# Power.net
KiCad netlist of a schematic drawn in Altium Designer
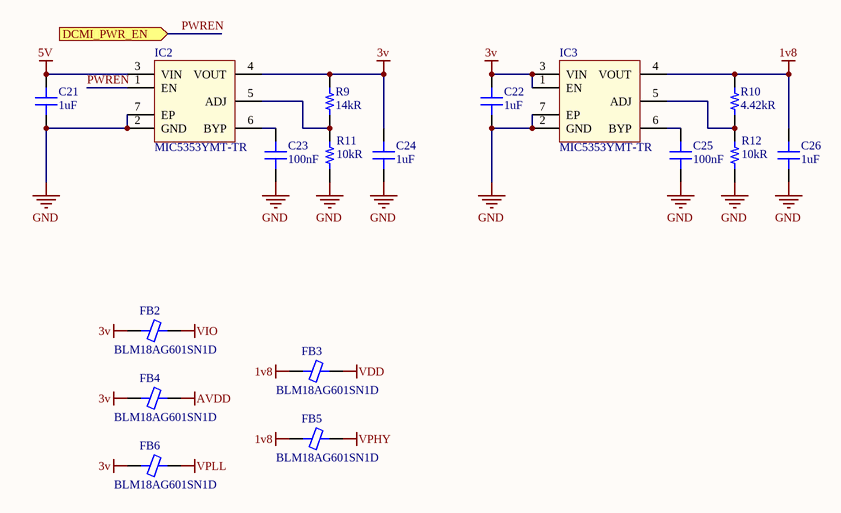
[diagram p0: Power.SchDoc]

(export (version "E")
  (design (tool "Eeschema 10.0.6"))
  (components
    (comp (ref "C21")
      (value "1uF")
      (footprint "CAP 0603/1608")
      (description "Ceramic, SMT Capacitor")
      (fields
        (field (name "MANUFACTURER") "Samsung")
        (field (name "MANUFACTURER PART NUMBER") "CL10A105KP8NNNC")
      )
      (libsource (lib "yildizIoT Library") (part "Capacitor - Ceramic"))
    )
    (comp (ref "C22")
      (value "1uF")
      (footprint "CAP 0603/1608")
      (description "Ceramic, SMT Capacitor")
      (fields
        (field (name "MANUFACTURER") "Samsung")
        (field (name "MANUFACTURER PART NUMBER") "CL10A105KP8NNNC")
      )
      (libsource (lib "yildizIoT Library") (part "Capacitor - Ceramic"))
    )
    (comp (ref "C23")
      (value "100nF")
      (footprint "CAP 0603/1608")
      (description "Ceramic, SMT Capacitor")
      (fields
        (field (name "MANUFACTURER") "Samsung")
        (field (name "MANUFACTURER PART NUMBER") "CL10B104JB8NNNC")
      )
      (libsource (lib "yildizIoT Library") (part "Capacitor - Ceramic"))
    )
    (comp (ref "C24")
      (value "1uF")
      (footprint "CAP 0603/1608")
      (description "Ceramic, SMT Capacitor")
      (fields
        (field (name "MANUFACTURER") "Samsung")
        (field (name "MANUFACTURER PART NUMBER") "CL10A105KP8NNNC")
      )
      (libsource (lib "yildizIoT Library") (part "Capacitor - Ceramic"))
    )
    (comp (ref "C25")
      (value "100nF")
      (footprint "CAP 0603/1608")
      (description "Ceramic, SMT Capacitor")
      (fields
        (field (name "MANUFACTURER") "Samsung")
        (field (name "MANUFACTURER PART NUMBER") "CL10B104JB8NNNC")
      )
      (libsource (lib "yildizIoT Library") (part "Capacitor - Ceramic"))
    )
    (comp (ref "C26")
      (value "1uF")
      (footprint "CAP 0603/1608")
      (description "Ceramic, SMT Capacitor")
      (fields
        (field (name "MANUFACTURER") "Samsung")
        (field (name "MANUFACTURER PART NUMBER") "CL10A105KP8NNNC")
      )
      (libsource (lib "yildizIoT Library") (part "Capacitor - Ceramic"))
    )
    (comp (ref "FB2")
      (value "BLM18AG601SN1D")
      (footprint "FER 0603/1608")
      (description "SMT Ferrite Chip")
      (fields (field (name "MANUFACTURER") "Murata") (field (name "TOLERANCE") "25%"))
      (libsource (lib "yildizIoT Library") (part "Ferrite Chip"))
    )
    (comp (ref "FB3")
      (value "BLM18AG601SN1D")
      (footprint "FER 0603/1608")
      (description "SMT Ferrite Chip")
      (fields (field (name "MANUFACTURER") "Murata") (field (name "TOLERANCE") "25%"))
      (libsource (lib "yildizIoT Library") (part "Ferrite Chip"))
    )
    (comp (ref "FB4")
      (value "BLM18AG601SN1D")
      (footprint "FER 0603/1608")
      (description "SMT Ferrite Chip")
      (fields (field (name "MANUFACTURER") "Murata") (field (name "TOLERANCE") "25%"))
      (libsource (lib "yildizIoT Library") (part "Ferrite Chip"))
    )
    (comp (ref "FB5")
      (value "BLM18AG601SN1D")
      (footprint "FER 0603/1608")
      (description "SMT Ferrite Chip")
      (fields (field (name "MANUFACTURER") "Murata") (field (name "TOLERANCE") "25%"))
      (libsource (lib "yildizIoT Library") (part "Ferrite Chip"))
    )
    (comp (ref "FB6")
      (value "BLM18AG601SN1D")
      (footprint "FER 0603/1608")
      (description "SMT Ferrite Chip")
      (fields (field (name "MANUFACTURER") "Murata") (field (name "TOLERANCE") "25%"))
      (libsource (lib "yildizIoT Library") (part "Ferrite Chip"))
    )
    (comp (ref "IC2")
      (value "MIC5353YMT-TR")
      (footprint "MICREL MLF-6 1.6x1.6MM")
      (description "Integrated Circuit")
      (fields (field (name "MANUFACTURER") "Microchip"))
      (libsource (lib "yildizIoT Library") (part "MICROCHIP MIC5353"))
    )
    (comp (ref "IC3")
      (value "MIC5353YMT-TR")
      (footprint "MICREL MLF-6 1.6x1.6MM")
      (description "Integrated Circuit")
      (fields (field (name "MANUFACTURER") "Microchip"))
      (libsource (lib "yildizIoT Library") (part "MICROCHIP MIC5353"))
    )
    (comp (ref "R9")
      (value "14kR")
      (footprint "RES 0603/1608")
      (description "Ceramic, SMT Capacitor")
      (fields
        (field (name "MANUFACTURER") "Yageo")
        (field (name "MANUFACTURER PART NUMBER") "RC0603FR-0714KL")
      )
      (libsource (lib "yildizIoT Library") (part "Resistor_Chip"))
    )
    (comp (ref "R10")
      (value "4.42kR")
      (footprint "RES 0603/1608")
      (description "Ceramic, SMT Capacitor")
      (fields
        (field (name "MANUFACTURER") "Yageo")
        (field (name "MANUFACTURER PART NUMBER") "RC0603FR-074K42L")
      )
      (libsource (lib "yildizIoT Library") (part "Resistor_Chip"))
    )
    (comp (ref "R11")
      (value "10kR")
      (footprint "RES 0603/1608")
      (description "Ceramic, SMT Capacitor")
      (fields
        (field (name "MANUFACTURER") "Stackpole Electronics")
        (field (name "MANUFACTURER PART NUMBER") "RNCP0603FTD10K0")
      )
      (libsource (lib "yildizIoT Library") (part "Resistor_Chip"))
    )
    (comp (ref "R12")
      (value "10kR")
      (footprint "RES 0603/1608")
      (description "Ceramic, SMT Capacitor")
      (fields
        (field (name "MANUFACTURER") "Stackpole Electronics")
        (field (name "MANUFACTURER PART NUMBER") "RNCP0603FTD10K0")
      )
      (libsource (lib "yildizIoT Library") (part "Resistor_Chip"))
    )
  )
  (nets
    (net (code "1") (name "/PWREN") (class "Default")
      (node (ref "IC2") (pin "1") (pinfunction "EN_1") (pintype "passive"))
    )
    (net (code "2") (name "1v8") (class "Default")
      (node (ref "C26") (pin "2") (pinfunction "2_2") (pintype "passive"))
      (node (ref "FB3") (pin "2") (pinfunction "2_2") (pintype "passive"))
      (node (ref "FB5") (pin "2") (pinfunction "2_2") (pintype "passive"))
      (node (ref "IC3") (pin "4") (pinfunction "VOUT_4") (pintype "passive"))
      (node (ref "R10") (pin "2") (pinfunction "2_2") (pintype "passive"))
    )
    (net (code "3") (name "3v") (class "Default")
      (node (ref "C22") (pin "2") (pinfunction "2_2") (pintype "passive"))
      (node (ref "C24") (pin "2") (pinfunction "2_2") (pintype "passive"))
      (node (ref "FB2") (pin "2") (pinfunction "2_2") (pintype "passive"))
      (node (ref "FB4") (pin "2") (pinfunction "2_2") (pintype "passive"))
      (node (ref "FB6") (pin "2") (pinfunction "2_2") (pintype "passive"))
      (node (ref "IC2") (pin "4") (pinfunction "VOUT_4") (pintype "passive"))
      (node (ref "IC3") (pin "1") (pinfunction "EN_1") (pintype "passive"))
      (node (ref "IC3") (pin "3") (pinfunction "VIN_3") (pintype "passive"))
      (node (ref "R9") (pin "2") (pinfunction "2_2") (pintype "passive"))
    )
    (net (code "4") (name "5V") (class "Default")
      (node (ref "C21") (pin "2") (pinfunction "2_2") (pintype "passive"))
      (node (ref "IC2") (pin "3") (pinfunction "VIN_3") (pintype "passive"))
    )
    (net (code "5") (name "AVDD") (class "Default")
      (node (ref "FB4") (pin "1") (pinfunction "1_1") (pintype "passive"))
    )
    (net (code "6") (name "GND") (class "Default")
      (node (ref "C21") (pin "1") (pinfunction "1_1") (pintype "passive"))
      (node (ref "C22") (pin "1") (pinfunction "1_1") (pintype "passive"))
      (node (ref "C23") (pin "1") (pinfunction "1_1") (pintype "passive"))
      (node (ref "C24") (pin "1") (pinfunction "1_1") (pintype "passive"))
      (node (ref "C25") (pin "1") (pinfunction "1_1") (pintype "passive"))
      (node (ref "C26") (pin "1") (pinfunction "1_1") (pintype "passive"))
      (node (ref "IC2") (pin "2") (pinfunction "GND_2") (pintype "passive"))
      (node (ref "IC2") (pin "7") (pinfunction "EP_7") (pintype "power_in"))
      (node (ref "IC3") (pin "2") (pinfunction "GND_2") (pintype "passive"))
      (node (ref "IC3") (pin "7") (pinfunction "EP_7") (pintype "power_in"))
      (node (ref "R11") (pin "2") (pinfunction "2_2") (pintype "passive"))
      (node (ref "R12") (pin "2") (pinfunction "2_2") (pintype "passive"))
    )
    (net (code "7") (name "Net-(IC2-ADJ)") (class "Default")
      (node (ref "IC2") (pin "5") (pinfunction "ADJ_5") (pintype "passive"))
      (node (ref "R11") (pin "1") (pinfunction "1_1") (pintype "passive"))
      (node (ref "R9") (pin "1") (pinfunction "1_1") (pintype "passive"))
    )
    (net (code "8") (name "Net-(IC2-BYP)") (class "Default")
      (node (ref "C23") (pin "2") (pinfunction "2_2") (pintype "passive"))
      (node (ref "IC2") (pin "6") (pinfunction "BYP_6") (pintype "passive"))
    )
    (net (code "9") (name "Net-(IC3-ADJ)") (class "Default")
      (node (ref "IC3") (pin "5") (pinfunction "ADJ_5") (pintype "passive"))
      (node (ref "R10") (pin "1") (pinfunction "1_1") (pintype "passive"))
      (node (ref "R12") (pin "1") (pinfunction "1_1") (pintype "passive"))
    )
    (net (code "10") (name "Net-(IC3-BYP)") (class "Default")
      (node (ref "C25") (pin "2") (pinfunction "2_2") (pintype "passive"))
      (node (ref "IC3") (pin "6") (pinfunction "BYP_6") (pintype "passive"))
    )
    (net (code "11") (name "VDD") (class "Default")
      (node (ref "FB3") (pin "1") (pinfunction "1_1") (pintype "passive"))
    )
    (net (code "12") (name "VIO") (class "Default")
      (node (ref "FB2") (pin "1") (pinfunction "1_1") (pintype "passive"))
    )
    (net (code "13") (name "VPHY") (class "Default")
      (node (ref "FB5") (pin "1") (pinfunction "1_1") (pintype "passive"))
    )
    (net (code "14") (name "VPLL") (class "Default")
      (node (ref "FB6") (pin "1") (pinfunction "1_1") (pintype "passive"))
    )
  )
)
